# PowerBoard.net
KiCad netlist of a schematic drawn in Altium Designer
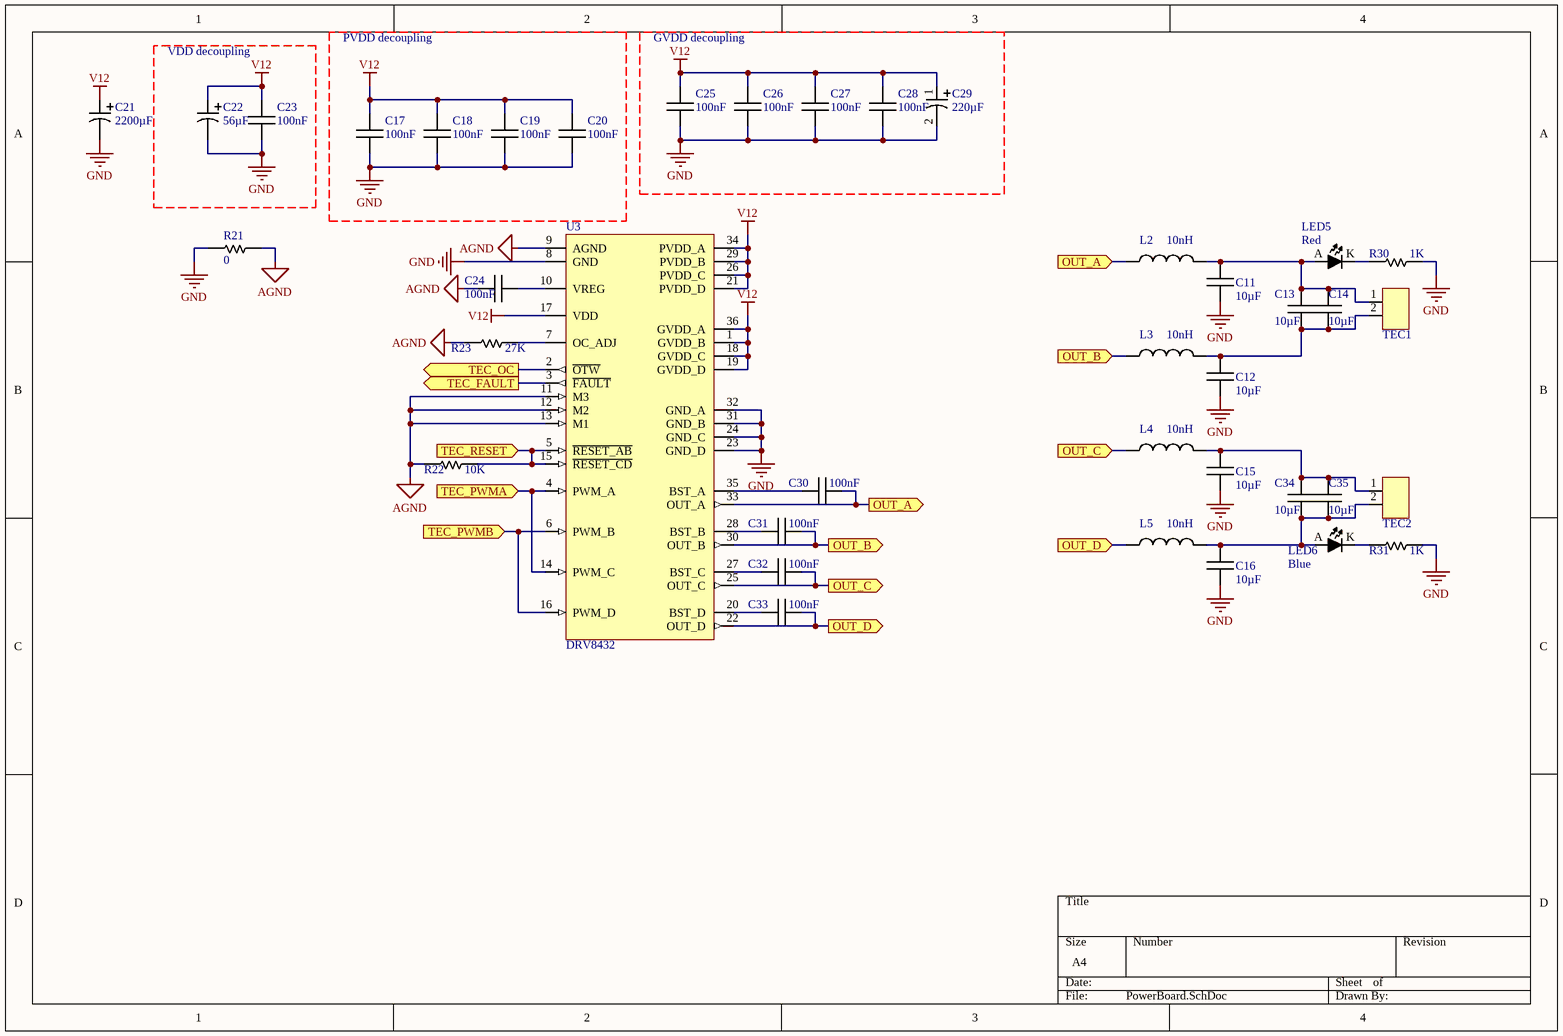
[diagram p0: PowerBoard.SchDoc]

(export (version "E")
  (design (tool "Eeschema 10.0.6"))
  (components
    (comp (ref "C11") (value "10µF") (footprint "CAPC3225N") (libsource (lib "Megaxone") (part "Capacitor")))
    (comp (ref "C12") (value "10µF") (footprint "CAPC3225N") (libsource (lib "Megaxone") (part "Capacitor")))
    (comp (ref "C13") (value "10µF") (footprint "CAPC3225N") (libsource (lib "Megaxone") (part "Capacitor")))
    (comp (ref "C14") (value "10µF") (footprint "CAPC3225N") (libsource (lib "Megaxone") (part "Capacitor")))
    (comp (ref "C15") (value "10µF") (footprint "CAPC3225N") (libsource (lib "Megaxone") (part "Capacitor")))
    (comp (ref "C16") (value "10µF") (footprint "CAPC3225N") (libsource (lib "Megaxone") (part "Capacitor")))
    (comp (ref "C17") (value "100nF") (footprint "CAPC1608N") (libsource (lib "Megaxone") (part "Capacitor")))
    (comp (ref "C18") (value "100nF") (footprint "CAPC1608N") (libsource (lib "Megaxone") (part "Capacitor")))
    (comp (ref "C19") (value "100nF") (footprint "CAPC1608N") (libsource (lib "Megaxone") (part "Capacitor")))
    (comp (ref "C20") (value "100nF") (footprint "CAPC1608N") (libsource (lib "Megaxone") (part "Capacitor")))
    (comp (ref "C21")
      (value "2200µF")
      (footprint "CAPPR7.5-18x35.5")
      (libsource (lib "Megaxone") (part "Capacitor Polarised"))
    )
    (comp (ref "C22")
      (value "56µF")
      (footprint "CAPPR2.5-6.3x15")
      (libsource (lib "Megaxone") (part "Capacitor Polarised"))
    )
    (comp (ref "C23") (value "100nF") (footprint "CAPC1608N") (libsource (lib "Megaxone") (part "Capacitor")))
    (comp (ref "C24") (value "100nF") (footprint "CAPC1608N") (libsource (lib "Megaxone") (part "Capacitor")))
    (comp (ref "C25") (value "100nF") (footprint "CAPC1608N") (libsource (lib "Megaxone") (part "Capacitor")))
    (comp (ref "C26") (value "100nF") (footprint "CAPC1608N") (libsource (lib "Megaxone") (part "Capacitor")))
    (comp (ref "C27") (value "100nF") (footprint "CAPC1608N") (libsource (lib "Megaxone") (part "Capacitor")))
    (comp (ref "C28") (value "100nF") (footprint "CAPC1608N") (libsource (lib "Megaxone") (part "Capacitor")))
    (comp (ref "C29")
      (value "220µF")
      (footprint "CAPPR3.5-8x15")
      (libsource (lib "") (part "Capacitor Polarised_1"))
    )
    (comp (ref "C30") (value "100nF") (footprint "CAPC1608N") (libsource (lib "Megaxone") (part "Capacitor")))
    (comp (ref "C31") (value "100nF") (footprint "CAPC1608N") (libsource (lib "Megaxone") (part "Capacitor")))
    (comp (ref "C32") (value "100nF") (footprint "CAPC1608N") (libsource (lib "Megaxone") (part "Capacitor")))
    (comp (ref "C33") (value "100nF") (footprint "CAPC1608N") (libsource (lib "Megaxone") (part "Capacitor")))
    (comp (ref "C34") (value "10µF") (footprint "CAPC3225N") (libsource (lib "Megaxone") (part "Capacitor")))
    (comp (ref "C35") (value "10µF") (footprint "CAPC3225N") (libsource (lib "Megaxone") (part "Capacitor")))
    (comp (ref "L2")
      (value "10nH")
      (footprint "Inductor 9.1×7.6mm TH")
      (libsource (lib "Megaxone") (part "Inductor"))
    )
    (comp (ref "L3")
      (value "10nH")
      (footprint "Inductor 9.1×7.6mm TH")
      (libsource (lib "Megaxone") (part "Inductor"))
    )
    (comp (ref "L4")
      (value "10nH")
      (footprint "Inductor 9.1×7.6mm TH")
      (libsource (lib "Megaxone") (part "Inductor"))
    )
    (comp (ref "L5")
      (value "10nH")
      (footprint "Inductor 9.1×7.6mm TH")
      (libsource (lib "Megaxone") (part "Inductor"))
    )
    (comp (ref "LED5") (value "Red") (footprint "LED 1608m") (libsource (lib "Megaxone") (part "LED")))
    (comp (ref "LED6") (value "Blue") (footprint "LED 1608m") (libsource (lib "Megaxone") (part "LED")))
    (comp (ref "R21") (value "0") (footprint "RESC1608N") (libsource (lib "Megaxone") (part "Resistor")))
    (comp (ref "R22") (value "10K") (footprint "RESC1608N") (libsource (lib "Megaxone") (part "Resistor")))
    (comp (ref "R23") (value "27K") (footprint "RESC2012N") (libsource (lib "Megaxone") (part "Resistor")))
    (comp (ref "R30") (value "1K") (footprint "RESC1608N") (libsource (lib "Megaxone") (part "Resistor")))
    (comp (ref "R31") (value "1K") (footprint "RESC1608N") (libsource (lib "Megaxone") (part "Resistor")))
    (comp (ref "TEC1")
      (value "High-Power Connector 2p")
      (footprint "High-Power Connector 2")
      (libsource (lib "Megaxone") (part "High-Power Connector 2p"))
    )
    (comp (ref "TEC2")
      (value "High-Power Connector 2p")
      (footprint "High-Power Connector 2")
      (libsource (lib "Megaxone") (part "High-Power Connector 2p"))
    )
    (comp (ref "U3") (value "DRV8432") (footprint "PSOP3-36") (libsource (lib "Megaxone") (part "DRV8432")))
  )
  (nets
    (net (code "1") (name "/OUT_A") (class "Default")
      (node (ref "C30") (pin "2") (pinfunction "2_2") (pintype "passive"))
      (node (ref "L2") (pin "1") (pinfunction "1_1") (pintype "passive"))
      (node (ref "U3") (pin "33") (pinfunction "OUT_A_33") (pintype "output"))
    )
    (net (code "2") (name "/OUT_B") (class "Default")
      (node (ref "C31") (pin "2") (pinfunction "2_2") (pintype "passive"))
      (node (ref "L3") (pin "1") (pinfunction "1_1") (pintype "passive"))
      (node (ref "U3") (pin "30") (pinfunction "OUT_B_30") (pintype "output"))
    )
    (net (code "3") (name "/OUT_C") (class "Default")
      (node (ref "C32") (pin "2") (pinfunction "2_2") (pintype "passive"))
      (node (ref "L4") (pin "1") (pinfunction "1_1") (pintype "passive"))
      (node (ref "U3") (pin "25") (pinfunction "OUT_C_25") (pintype "output"))
    )
    (net (code "4") (name "/OUT_D") (class "Default")
      (node (ref "C33") (pin "2") (pinfunction "2_2") (pintype "passive"))
      (node (ref "L5") (pin "1") (pinfunction "1_1") (pintype "passive"))
      (node (ref "U3") (pin "22") (pinfunction "OUT_D_22") (pintype "output"))
    )
    (net (code "5") (name "/TEC_FAULT") (class "Default")
      (node (ref "U3") (pin "3") (pinfunction "~{FAULT}_3") (pintype "output"))
    )
    (net (code "6") (name "/TEC_OC") (class "Default")
      (node (ref "U3") (pin "2") (pinfunction "~{OTW}_2") (pintype "output"))
    )
    (net (code "7") (name "/TEC_PWMA") (class "Default")
      (node (ref "U3") (pin "14") (pinfunction "PWM_C_14") (pintype "input"))
      (node (ref "U3") (pin "4") (pinfunction "PWM_A_4") (pintype "input"))
    )
    (net (code "8") (name "/TEC_PWMB") (class "Default")
      (node (ref "U3") (pin "16") (pinfunction "PWM_D_16") (pintype "input"))
      (node (ref "U3") (pin "6") (pinfunction "PWM_B_6") (pintype "input"))
    )
    (net (code "9") (name "/TEC_RESET") (class "Default")
      (node (ref "R22") (pin "2") (pinfunction "2_2") (pintype "passive"))
      (node (ref "U3") (pin "15") (pinfunction "~{RESET_CD}_15") (pintype "input"))
      (node (ref "U3") (pin "5") (pinfunction "~{RESET_AB}_5") (pintype "input"))
    )
    (net (code "10") (name "AGND") (class "Default")
      (node (ref "C24") (pin "2") (pinfunction "2_2") (pintype "passive"))
      (node (ref "R21") (pin "2") (pinfunction "2_2") (pintype "passive"))
      (node (ref "R22") (pin "1") (pinfunction "1_1") (pintype "passive"))
      (node (ref "R23") (pin "1") (pinfunction "1_1") (pintype "passive"))
      (node (ref "U3") (pin "11") (pinfunction "M3_11") (pintype "input"))
      (node (ref "U3") (pin "12") (pinfunction "M2_12") (pintype "input"))
      (node (ref "U3") (pin "13") (pinfunction "M1_13") (pintype "input"))
      (node (ref "U3") (pin "9") (pinfunction "AGND_9") (pintype "power_in"))
    )
    (net (code "11") (name "GND") (class "Default")
      (node (ref "C11") (pin "1") (pinfunction "1_1") (pintype "passive"))
      (node (ref "C12") (pin "1") (pinfunction "1_1") (pintype "passive"))
      (node (ref "C15") (pin "1") (pinfunction "1_1") (pintype "passive"))
      (node (ref "C16") (pin "1") (pinfunction "1_1") (pintype "passive"))
      (node (ref "C17") (pin "1") (pinfunction "1_1") (pintype "passive"))
      (node (ref "C18") (pin "1") (pinfunction "1_1") (pintype "passive"))
      (node (ref "C19") (pin "1") (pinfunction "1_1") (pintype "passive"))
      (node (ref "C20") (pin "1") (pinfunction "1_1") (pintype "passive"))
      (node (ref "C21") (pin "2") (pinfunction "2_2") (pintype "passive"))
      (node (ref "C22") (pin "2") (pinfunction "2_2") (pintype "passive"))
      (node (ref "C23") (pin "1") (pinfunction "1_1") (pintype "passive"))
      (node (ref "C25") (pin "1") (pinfunction "1_1") (pintype "passive"))
      (node (ref "C26") (pin "1") (pinfunction "1_1") (pintype "passive"))
      (node (ref "C27") (pin "1") (pinfunction "1_1") (pintype "passive"))
      (node (ref "C28") (pin "1") (pinfunction "1_1") (pintype "passive"))
      (node (ref "C29") (pin "2") (pinfunction "2_2") (pintype "passive"))
      (node (ref "R21") (pin "1") (pinfunction "1_1") (pintype "passive"))
      (node (ref "R30") (pin "2") (pinfunction "2_2") (pintype "passive"))
      (node (ref "R31") (pin "2") (pinfunction "2_2") (pintype "passive"))
      (node (ref "U3") (pin "23") (pinfunction "GND_D_23") (pintype "power_in"))
      (node (ref "U3") (pin "24") (pinfunction "GND_C_24") (pintype "power_in"))
      (node (ref "U3") (pin "31") (pinfunction "GND_B_31") (pintype "power_in"))
      (node (ref "U3") (pin "32") (pinfunction "GND_A_32") (pintype "power_in"))
      (node (ref "U3") (pin "8") (pinfunction "GND_8") (pintype "power_in"))
    )
    (net (code "12") (name "Net-(C11-Pad2)") (class "Default")
      (node (ref "C11") (pin "2") (pinfunction "2_2") (pintype "passive"))
      (node (ref "C13") (pin "2") (pinfunction "2_2") (pintype "passive"))
      (node (ref "C14") (pin "2") (pinfunction "2_2") (pintype "passive"))
      (node (ref "L2") (pin "2") (pinfunction "2_2") (pintype "passive"))
      (node (ref "LED5") (pin "A") (pinfunction "A_A") (pintype "passive"))
      (node (ref "TEC1") (pin "1") (pinfunction "1_1") (pintype "power_in"))
    )
    (net (code "13") (name "Net-(C12-Pad2)") (class "Default")
      (node (ref "C12") (pin "2") (pinfunction "2_2") (pintype "passive"))
      (node (ref "C13") (pin "1") (pinfunction "1_1") (pintype "passive"))
      (node (ref "C14") (pin "1") (pinfunction "1_1") (pintype "passive"))
      (node (ref "L3") (pin "2") (pinfunction "2_2") (pintype "passive"))
      (node (ref "TEC1") (pin "2") (pinfunction "2_2") (pintype "power_in"))
    )
    (net (code "14") (name "Net-(C15-Pad2)") (class "Default")
      (node (ref "C15") (pin "2") (pinfunction "2_2") (pintype "passive"))
      (node (ref "C34") (pin "2") (pinfunction "2_2") (pintype "passive"))
      (node (ref "C35") (pin "2") (pinfunction "2_2") (pintype "passive"))
      (node (ref "L4") (pin "2") (pinfunction "2_2") (pintype "passive"))
      (node (ref "TEC2") (pin "1") (pinfunction "1_1") (pintype "power_in"))
    )
    (net (code "15") (name "Net-(C16-Pad2)") (class "Default")
      (node (ref "C16") (pin "2") (pinfunction "2_2") (pintype "passive"))
      (node (ref "C34") (pin "1") (pinfunction "1_1") (pintype "passive"))
      (node (ref "C35") (pin "1") (pinfunction "1_1") (pintype "passive"))
      (node (ref "L5") (pin "2") (pinfunction "2_2") (pintype "passive"))
      (node (ref "LED6") (pin "A") (pinfunction "A_A") (pintype "passive"))
      (node (ref "TEC2") (pin "2") (pinfunction "2_2") (pintype "power_in"))
    )
    (net (code "16") (name "Net-(LED5-PadK)") (class "Default")
      (node (ref "LED5") (pin "K") (pinfunction "K_K") (pintype "passive"))
      (node (ref "R30") (pin "1") (pinfunction "1_1") (pintype "passive"))
    )
    (net (code "17") (name "Net-(LED6-PadK)") (class "Default")
      (node (ref "LED6") (pin "K") (pinfunction "K_K") (pintype "passive"))
      (node (ref "R31") (pin "1") (pinfunction "1_1") (pintype "passive"))
    )
    (net (code "18") (name "Net-(U3-BST_A)") (class "Default")
      (node (ref "C30") (pin "1") (pinfunction "1_1") (pintype "passive"))
      (node (ref "U3") (pin "35") (pinfunction "BST_A_35") (pintype "passive"))
    )
    (net (code "19") (name "Net-(U3-BST_B)") (class "Default")
      (node (ref "C31") (pin "1") (pinfunction "1_1") (pintype "passive"))
      (node (ref "U3") (pin "28") (pinfunction "BST_B_28") (pintype "passive"))
    )
    (net (code "20") (name "Net-(U3-BST_C)") (class "Default")
      (node (ref "C32") (pin "1") (pinfunction "1_1") (pintype "passive"))
      (node (ref "U3") (pin "27") (pinfunction "BST_C_27") (pintype "passive"))
    )
    (net (code "21") (name "Net-(U3-BST_D)") (class "Default")
      (node (ref "C33") (pin "1") (pinfunction "1_1") (pintype "passive"))
      (node (ref "U3") (pin "20") (pinfunction "BST_D_20") (pintype "passive"))
    )
    (net (code "22") (name "Net-(U3-OC_ADJ)") (class "Default")
      (node (ref "R23") (pin "2") (pinfunction "2_2") (pintype "passive"))
      (node (ref "U3") (pin "7") (pinfunction "OC_ADJ_7") (pintype "passive"))
    )
    (net (code "23") (name "Net-(U3-VREG)") (class "Default")
      (node (ref "C24") (pin "1") (pinfunction "1_1") (pintype "passive"))
      (node (ref "U3") (pin "10") (pinfunction "VREG_10") (pintype "power_in"))
    )
    (net (code "24") (name "V12") (class "Default")
      (node (ref "C17") (pin "2") (pinfunction "2_2") (pintype "passive"))
      (node (ref "C18") (pin "2") (pinfunction "2_2") (pintype "passive"))
      (node (ref "C19") (pin "2") (pinfunction "2_2") (pintype "passive"))
      (node (ref "C20") (pin "2") (pinfunction "2_2") (pintype "passive"))
      (node (ref "C21") (pin "1") (pinfunction "1_1") (pintype "passive"))
      (node (ref "C22") (pin "1") (pinfunction "1_1") (pintype "passive"))
      (node (ref "C23") (pin "2") (pinfunction "2_2") (pintype "passive"))
      (node (ref "C25") (pin "2") (pinfunction "2_2") (pintype "passive"))
      (node (ref "C26") (pin "2") (pinfunction "2_2") (pintype "passive"))
      (node (ref "C27") (pin "2") (pinfunction "2_2") (pintype "passive"))
      (node (ref "C28") (pin "2") (pinfunction "2_2") (pintype "passive"))
      (node (ref "C29") (pin "1") (pinfunction "1_1") (pintype "passive"))
      (node (ref "U3") (pin "1") (pinfunction "GVDD_B_1") (pintype "power_in"))
      (node (ref "U3") (pin "17") (pinfunction "VDD_17") (pintype "power_in"))
      (node (ref "U3") (pin "18") (pinfunction "GVDD_C_18") (pintype "power_in"))
      (node (ref "U3") (pin "19") (pinfunction "GVDD_D_19") (pintype "power_in"))
      (node (ref "U3") (pin "21") (pinfunction "PVDD_D_21") (pintype "power_in"))
      (node (ref "U3") (pin "26") (pinfunction "PVDD_C_26") (pintype "power_in"))
      (node (ref "U3") (pin "29") (pinfunction "PVDD_B_29") (pintype "power_in"))
      (node (ref "U3") (pin "34") (pinfunction "PVDD_A_34") (pintype "power_in"))
      (node (ref "U3") (pin "36") (pinfunction "GVDD_A_36") (pintype "power_in"))
    )
  )
)
